# PROC051D_VPP_Supply.net
KiCad netlist of a schematic drawn in Altium Designer
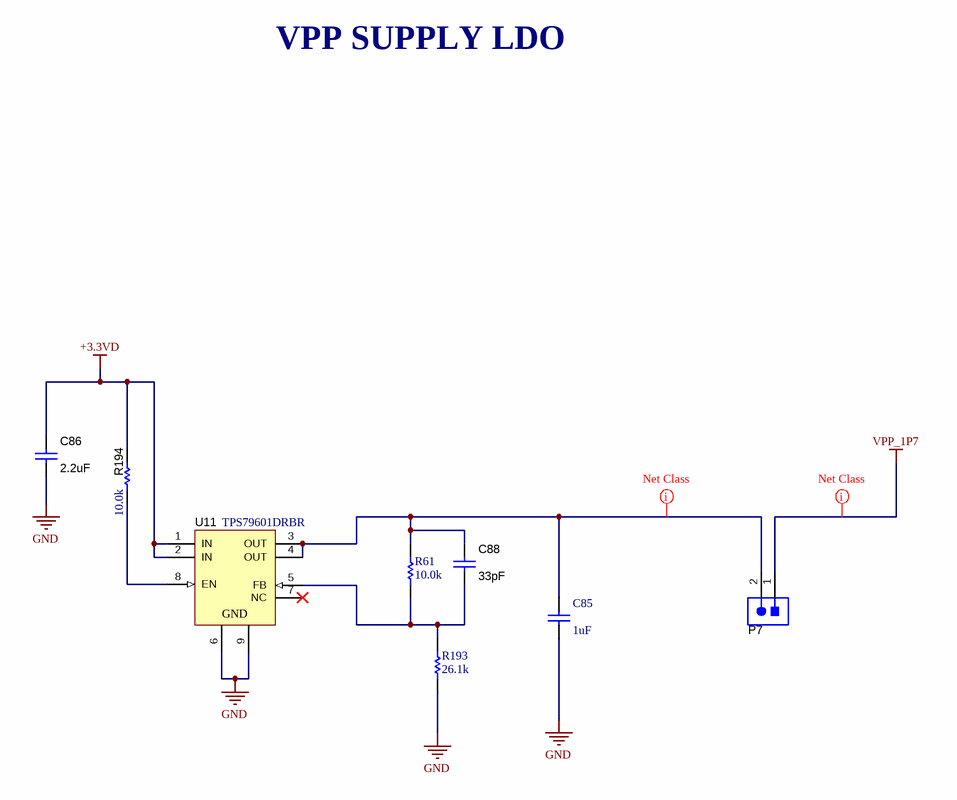
[diagram p0: PROC051D_VPP_Supply.SchDoc]

(export (version "E")
  (design (tool "Eeschema 10.0.6"))
  (components
    (comp (ref "C85")
      (value "GRM155R70J105MA12D")
      (footprint "0402")
      (description "CAP, CERM, 1 uF, 6.3 V, +/- 20%, X7R, 0402")
      (fields
        (field (name "MANUFACTURER") "MuRata")
        (field (name "VALUEDISPLAYED") "1uF")
        (field (name "PUBLISHER") "Texas Instruments")
      )
      (libsource (lib "Altium Vault - TI") (part "Capacitor"))
    )
    (comp (ref "C86")
      (value "C1005X7S1A225K050BC")
      (footprint "0402_065L")
      (description "CAP, CERM, 2.2 uF, 10 V, +/- 10%, X7S, 0402")
      (fields
        (field (name "MANUFACTURER") "TDK")
        (field (name "VALUEDISPLAYED") "2.2uF")
        (field (name "PUBLISHER") "Texas Instruments")
      )
      (libsource (lib "Altium Vault - TI") (part "CMP-0006302-2"))
    )
    (comp (ref "C88")
      (value "C0402C330J5GAC")
      (footprint "0402L")
      (description "CAP, CERM, 33 pF, 50 V, +/- 5%, C0G/NP0, 0402")
      (fields
        (field (name "MANUFACTURER") "Kemet")
        (field (name "VALUEDISPLAYED") "33pF")
        (field (name "PUBLISHER") "Texas Instruments")
      )
      (libsource (lib "Altium Vault - TI") (part "Capacitor"))
    )
    (comp (ref "P7")
      (value "TSW-102-07-G-S")
      (footprint "TSW-102-07-G-S")
      (description "Header, 100mil, 2x1, Gold, TH")
      (fields (field (name "MANUFACTURER") "Samtec"))
      (libsource (lib "Altium Vault - TI") (part "Header_2x1"))
    )
    (comp (ref "R61")
      (value "ERJ-2RKF1002X")
      (footprint "0402")
      (description "RES, 10.0 k, 1%, 0.1 W, 0402")
      (fields
        (field (name "MANUFACTURER") "Panasonic")
        (field (name "VALUEDISPLAYED") "10.0k")
        (field (name "PUBLISHER") "Texas Instruments")
      )
      (libsource (lib "Altium Vault - TI") (part "Resistor"))
    )
    (comp (ref "R193")
      (value "CRCW040226K1FKED")
      (footprint "0402")
      (description "RES, 26.1 k, 1%, 0.063 W, AEC-Q200 Grade 0, 0402")
      (fields (field (name "MANUFACTURER") "Vishay-Dale") (field (name "VALUEDISPLAYED") "26.1k"))
      (libsource (lib "Altium Vault - TI") (part "Resistor"))
    )
    (comp (ref "R194")
      (value "CRCW040210K0FKED")
      (footprint "0402L")
      (description "RES, 10.0 k, 1%, 0.063 W, AEC-Q200 Grade 0, 0402")
      (fields (field (name "MANUFACTURER") "Vishay-Dale") (field (name "VALUEDISPLAYED") "10.0k"))
      (libsource (lib "Altium Vault - TI") (part "Resistor"))
    )
    (comp (ref "U11")
      (value "TPS79601DRBR")
      (footprint "DRB0008B")
      (fields (field (name "MANUFACTURER") "Texas Instruments") (field (name "PARTNUMBER") "TPS79601DRBR"))
      (libsource (lib "Altium Vault - TI") (part "CMP-0036402-3"))
    )
  )
  (nets
    (net (code "1") (name "+3.3VD") (class "Default")
      (node (ref "C86") (pin "2") (pinfunction "2_2") (pintype "passive"))
      (node (ref "R194") (pin "1") (pinfunction "1_1") (pintype "passive"))
      (node (ref "U11") (pin "1") (pinfunction "IN_1") (pintype "power_in"))
      (node (ref "U11") (pin "2") (pinfunction "IN_2") (pintype "power_in"))
    )
    (net (code "2") (name "GND") (class "Default")
      (node (ref "C85") (pin "2") (pinfunction "2_2") (pintype "passive"))
      (node (ref "C86") (pin "1") (pinfunction "1_1") (pintype "passive"))
      (node (ref "R193") (pin "1") (pinfunction "1_1") (pintype "passive"))
      (node (ref "U11") (pin "6") (pinfunction "GND_6") (pintype "power_in"))
      (node (ref "U11") (pin "9") (pinfunction "GND_9") (pintype "power_in"))
    )
    (net (code "3") (name "Net-(C85-Pad1)") (class "Default")
      (node (ref "C85") (pin "1") (pinfunction "1_1") (pintype "passive"))
      (node (ref "C88") (pin "1") (pinfunction "1_1") (pintype "passive"))
      (node (ref "P7") (pin "2") (pinfunction "2_2") (pintype "passive"))
      (node (ref "R61") (pin "2") (pinfunction "2_2") (pintype "passive"))
      (node (ref "U11") (pin "3") (pinfunction "OUT_3") (pintype "power_in"))
      (node (ref "U11") (pin "4") (pinfunction "OUT_4") (pintype "power_in"))
    )
    (net (code "4") (name "Net-(U11-EN)") (class "Default")
      (node (ref "R194") (pin "2") (pinfunction "2_2") (pintype "passive"))
      (node (ref "U11") (pin "8") (pinfunction "EN_8") (pintype "input"))
    )
    (net (code "5") (name "Net-(U11-FB)") (class "Default")
      (node (ref "C88") (pin "2") (pinfunction "2_2") (pintype "passive"))
      (node (ref "R193") (pin "2") (pinfunction "2_2") (pintype "passive"))
      (node (ref "R61") (pin "1") (pinfunction "1_1") (pintype "passive"))
      (node (ref "U11") (pin "5") (pinfunction "FB_5") (pintype "input"))
    )
    (net (code "6") (name "VPP_1P7") (class "Default")
      (node (ref "P7") (pin "1") (pinfunction "1_1") (pintype "passive"))
    )
    (net (code "7") (name "unconnected-(U11-NC-Pad7)") (class "Default")
      (node (ref "U11") (pin "7") (pinfunction "NC_7") (pintype "passive+no_connect"))
    )
  )
)
